# Sheet1.net
KiCad netlist of a schematic drawn in Altium Designer
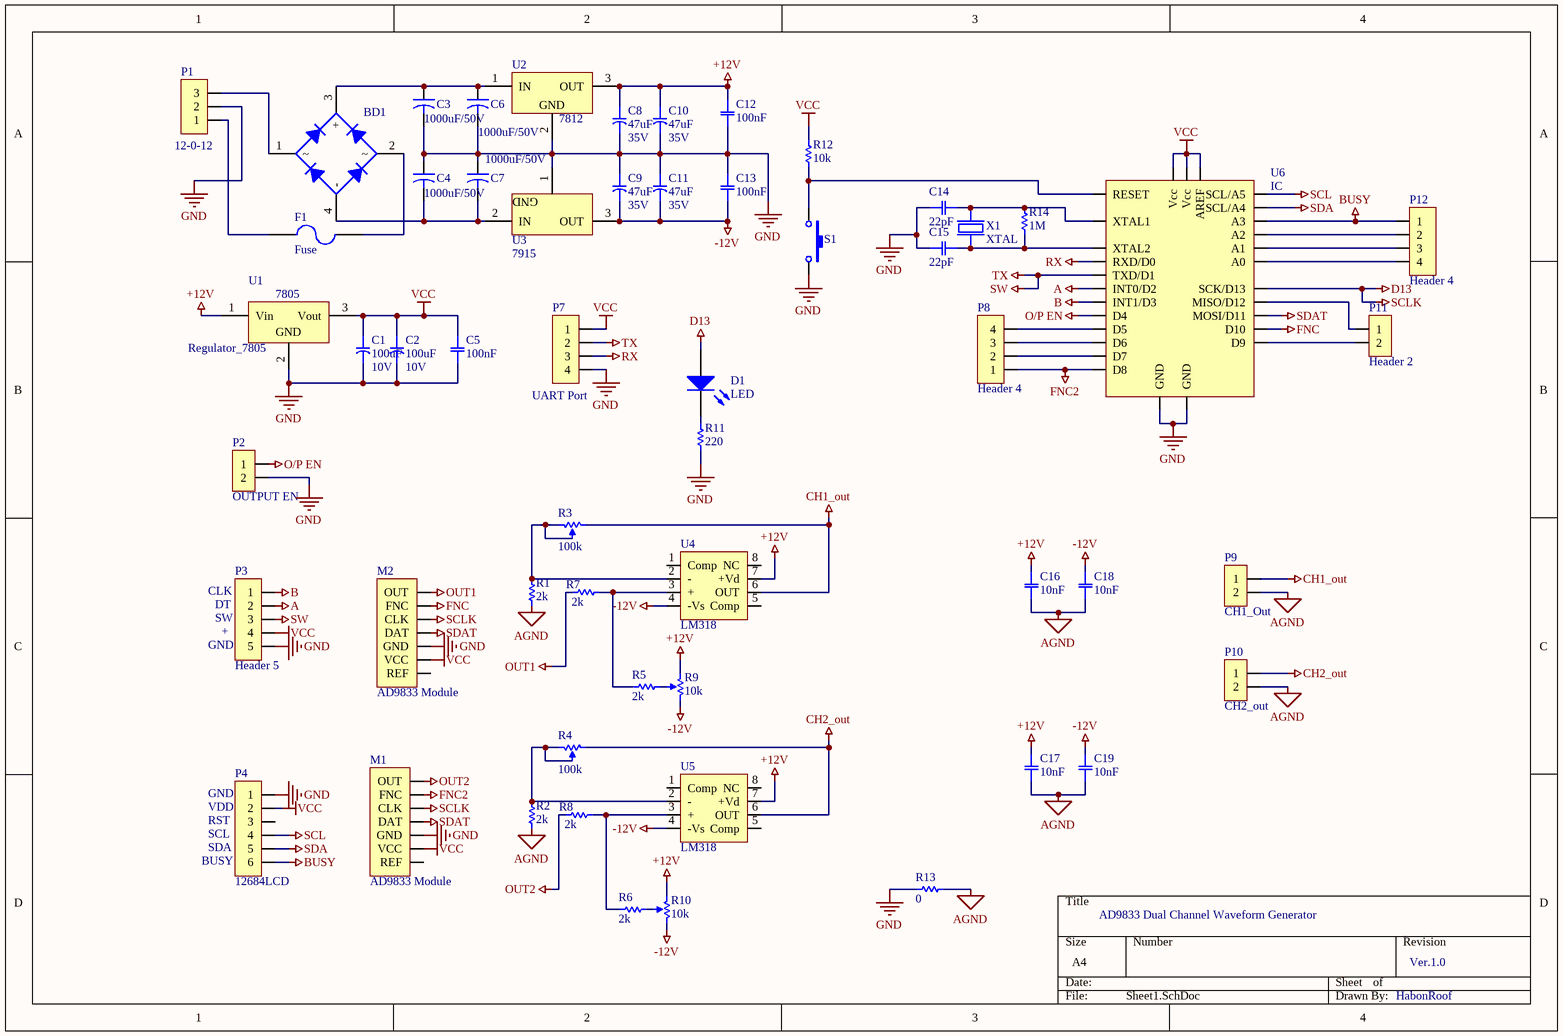
[diagram p0: Sheet1.SchDoc]

(export (version "E")
  (design (tool "Eeschema 10.0.6"))
  (components
    (comp (ref "BD1")
      (value "Bridge")
      (footprint "Bridge_KBL406")
      (description "全波整流器")
      (fields (field (name "PUBLISHER") "Altium Limited"))
      (libsource (lib "Johnson_Lib") (part "Bridge"))
    )
    (comp (ref "C1")
      (value "100uF")
      (footprint "Capacitor_Electrolytic:RAD-100_200")
      (description "JACKON LHK General Purpose")
      (fields
        (field (name "VOLTATGE") "10V")
        (field (name "Comment") "JACKON LHK 100uF/10V")
        (field (name "PUBLISHER") "Altium Limited")
      )
      (libsource (lib "Capacitor_Electrolytic") (part "JACKON LHK 100uF/10V"))
    )
    (comp (ref "C2")
      (value "100uF")
      (footprint "Capacitor_Electrolytic:RAD-100_200")
      (description "JACKON LHK General Purpose")
      (fields
        (field (name "VOLTATGE") "10V")
        (field (name "Comment") "JACKON LHK 100uF/10V")
        (field (name "PUBLISHER") "Altium Limited")
      )
      (libsource (lib "Capacitor_Electrolytic") (part "JACKON LHK 100uF/10V"))
    )
    (comp (ref "C3")
      (value "1000uF/50V")
      (footprint "Cap_M_1000uF/50V")
      (description "有極性電解電容(中)")
      (fields (field (name "PUBLISHER") "Altium Limited"))
      (libsource (lib "Johnson_Lib") (part "Cap_EC_Medium"))
    )
    (comp (ref "C4")
      (value "1000uF/50V")
      (footprint "Cap_M_1000uF/50V")
      (description "有極性電解電容(中)")
      (fields (field (name "PUBLISHER") "Altium Limited"))
      (libsource (lib "Johnson_Lib") (part "Cap_EC_Medium"))
    )
    (comp (ref "C5")
      (value "100nF")
      (footprint "Capacitor_Metallized_Polyester_Film:CAP-200_100*300")
      (description "Metallized Polyester Film Capacitor")
      (fields (field (name "Comment") "100n/100V") (field (name "PUBLISHER") "Altium Limited"))
      (libsource (lib "Capacitor_Metallized_Polyester_Film") (part "100n/100V"))
    )
    (comp (ref "C6")
      (value "1000uF/50V")
      (footprint "Cap_M_1000uF/50V")
      (description "有極性電解電容(中)")
      (fields (field (name "PUBLISHER") "Altium Limited"))
      (libsource (lib "Johnson_Lib") (part "Cap_EC_Medium"))
    )
    (comp (ref "C7")
      (value "1000uF/50V")
      (footprint "Cap_M_1000uF/50V")
      (description "有極性電解電容(中)")
      (fields (field (name "PUBLISHER") "Altium Limited"))
      (libsource (lib "Johnson_Lib") (part "Cap_EC_Medium"))
    )
    (comp (ref "C8")
      (value "47uF")
      (footprint "Capacitor_Electrolytic:RAD-100_200")
      (description "JACKON LHK General Purpose")
      (fields
        (field (name "VOLTATGE") "35V")
        (field (name "Comment") "JACKON LHK 47uF/35V")
        (field (name "PUBLISHER") "Altium Limited")
      )
      (libsource (lib "Capacitor_Electrolytic") (part "JACKON LHK 47uF/35V"))
    )
    (comp (ref "C9")
      (value "47uF")
      (footprint "Capacitor_Electrolytic:RAD-100_200")
      (description "JACKON LHK General Purpose")
      (fields
        (field (name "VOLTATGE") "35V")
        (field (name "Comment") "JACKON LHK 47uF/35V")
        (field (name "PUBLISHER") "Altium Limited")
      )
      (libsource (lib "Capacitor_Electrolytic") (part "JACKON LHK 47uF/35V"))
    )
    (comp (ref "C10")
      (value "47uF")
      (footprint "Capacitor_Electrolytic:RAD-100_200")
      (description "JACKON LHK General Purpose")
      (fields
        (field (name "VOLTATGE") "35V")
        (field (name "Comment") "JACKON LHK 47uF/35V")
        (field (name "PUBLISHER") "Altium Limited")
      )
      (libsource (lib "Capacitor_Electrolytic") (part "JACKON LHK 47uF/35V"))
    )
    (comp (ref "C11")
      (value "47uF")
      (footprint "Capacitor_Electrolytic:RAD-100_200")
      (description "JACKON LHK General Purpose")
      (fields
        (field (name "VOLTATGE") "35V")
        (field (name "Comment") "JACKON LHK 47uF/35V")
        (field (name "PUBLISHER") "Altium Limited")
      )
      (libsource (lib "Capacitor_Electrolytic") (part "JACKON LHK 47uF/35V"))
    )
    (comp (ref "C12")
      (value "100nF")
      (footprint "Capacitor_Metallized_Polyester_Film:CAP-200_100*300")
      (description "Metallized Polyester Film Capacitor")
      (fields (field (name "Comment") "100n/100V") (field (name "PUBLISHER") "Altium Limited"))
      (libsource (lib "Capacitor_Metallized_Polyester_Film") (part "100n/100V"))
    )
    (comp (ref "C13")
      (value "100nF")
      (footprint "Capacitor_Metallized_Polyester_Film:CAP-200_100*300")
      (description "Metallized Polyester Film Capacitor")
      (fields (field (name "Comment") "100n/100V") (field (name "PUBLISHER") "Altium Limited"))
      (libsource (lib "Capacitor_Metallized_Polyester_Film") (part "100n/100V"))
    )
    (comp (ref "C14")
      (value "22pF")
      (footprint "Capacitor_Ceramic:CAP-200_100*300")
      (description "Ceramic Capacitor")
      (fields (field (name "Comment") "22p/1kV") (field (name "PUBLISHER") "Altium Limited"))
      (libsource (lib "Capacitor_Ceramic") (part "22p/1kV"))
    )
    (comp (ref "C15")
      (value "22pF")
      (footprint "Capacitor_Ceramic:CAP-200_100*300")
      (description "Ceramic Capacitor")
      (fields (field (name "Comment") "22p/1kV") (field (name "PUBLISHER") "Altium Limited"))
      (libsource (lib "Capacitor_Ceramic") (part "22p/1kV"))
    )
    (comp (ref "C16")
      (value "10nF")
      (footprint "Capacitor_Metallized_Polyester_Film:CAP-200_100*300")
      (description "Metallized Polyester Film Capacitor")
      (fields (field (name "Comment") "100n/100V") (field (name "PUBLISHER") "Altium Limited"))
      (libsource (lib "Capacitor_Metallized_Polyester_Film") (part "100n/100V"))
    )
    (comp (ref "C17")
      (value "10nF")
      (footprint "Capacitor_Metallized_Polyester_Film:CAP-200_100*300")
      (description "Metallized Polyester Film Capacitor")
      (fields (field (name "Comment") "100n/100V") (field (name "PUBLISHER") "Altium Limited"))
      (libsource (lib "Capacitor_Metallized_Polyester_Film") (part "100n/100V"))
    )
    (comp (ref "C18")
      (value "10nF")
      (footprint "Capacitor_Metallized_Polyester_Film:CAP-200_100*300")
      (description "Metallized Polyester Film Capacitor")
      (fields (field (name "Comment") "100n/100V") (field (name "PUBLISHER") "Altium Limited"))
      (libsource (lib "Capacitor_Metallized_Polyester_Film") (part "100n/100V"))
    )
    (comp (ref "C19")
      (value "10nF")
      (footprint "Capacitor_Metallized_Polyester_Film:CAP-200_100*300")
      (description "Metallized Polyester Film Capacitor")
      (fields (field (name "Comment") "100n/100V") (field (name "PUBLISHER") "Altium Limited"))
      (libsource (lib "Capacitor_Metallized_Polyester_Film") (part "100n/100V"))
    )
    (comp (ref "D1")
      (value "LED")
      (footprint "LED_SMALL")
      (fields (field (name "PUBLISHER") "Altium Limited"))
      (libsource (lib "Johnson_Lib") (part "LED"))
    )
    (comp (ref "F1")
      (value "Fuse")
      (footprint "FUSE")
      (fields (field (name "PUBLISHER") "Altium Limited"))
      (libsource (lib "Johnson_Lib") (part "Fuse"))
    )
    (comp (ref "M1")
      (value "AD9833 Module")
      (footprint "AD9833")
      (libsource (lib "Johnson_Lib") (part "AD9833 Module"))
    )
    (comp (ref "M2")
      (value "AD9833 Module")
      (footprint "AD9833")
      (libsource (lib "Johnson_Lib") (part "AD9833 Module"))
    )
    (comp (ref "P1")
      (value "12-0-12")
      (footprint "HDR1X3")
      (description "Header, 3-Pin")
      (fields (field (name "PUBLISHER") "Altium Limited"))
      (libsource (lib "Johnson_Lib") (part "Header 3"))
    )
    (comp (ref "P2")
      (value "OUTPUT EN")
      (footprint "HDR1X2")
      (description "Header, 2-Pin")
      (fields (field (name "PUBLISHER") "Altium Limited"))
      (libsource (lib "Johnson_Lib") (part "Header 2"))
    )
    (comp (ref "P3")
      (value "Header 5")
      (footprint "HDR1X5")
      (description "Header, 5-Pin")
      (fields (field (name "PUBLISHER") "Altium Limited"))
      (libsource (lib "Johnson_Lib") (part "Header 5"))
    )
    (comp (ref "P4")
      (value "12684LCD")
      (footprint "HDR1X6")
      (description "Header, 6-Pin")
      (fields (field (name "PUBLISHER") "Altium Limited"))
      (libsource (lib "Johnson_Lib") (part "Header 6"))
    )
    (comp (ref "P7")
      (value "UART Port")
      (footprint "HDR1X4H")
      (description "Header, 4-Pin")
      (fields (field (name "PUBLISHER") "Altium Limited"))
      (libsource (lib "") (part "Header 4_1"))
    )
    (comp (ref "P8")
      (value "Header 4")
      (footprint "HDR1X4")
      (description "Header, 4-Pin")
      (fields (field (name "PUBLISHER") "Altium Limited"))
      (libsource (lib "") (part "Header 4_2"))
    )
    (comp (ref "P9")
      (value "CH1_Out")
      (footprint "HDR1X2")
      (description "Header, 2-Pin")
      (fields (field (name "PUBLISHER") "Altium Limited"))
      (libsource (lib "Johnson_Lib") (part "Header 2"))
    )
    (comp (ref "P10")
      (value "CH2_out")
      (footprint "HDR1X2")
      (description "Header, 2-Pin")
      (fields (field (name "PUBLISHER") "Altium Limited"))
      (libsource (lib "Johnson_Lib") (part "Header 2"))
    )
    (comp (ref "P11")
      (value "Header 2")
      (footprint "HDR1X2")
      (description "Header, 2-Pin")
      (fields (field (name "PUBLISHER") "Altium Limited"))
      (libsource (lib "") (part "Header 2_1"))
    )
    (comp (ref "P12")
      (value "Header 4")
      (footprint "HDR1X4")
      (description "Header, 4-Pin")
      (fields (field (name "PUBLISHER") "Altium Limited"))
      (libsource (lib "Johnson_Lib") (part "Header 4"))
    )
    (comp (ref "R1")
      (value "2k")
      (footprint "R-0.25W")
      (description "固定電阻")
      (fields (field (name "PUBLISHER") "Altium Limited"))
      (libsource (lib "Johnson_Lib") (part "Resistor"))
    )
    (comp (ref "R2")
      (value "2k")
      (footprint "R-0.25W")
      (description "固定電阻")
      (fields (field (name "PUBLISHER") "Altium Limited"))
      (libsource (lib "Johnson_Lib") (part "Resistor"))
    )
    (comp (ref "R3")
      (value "100k")
      (footprint "VR-Medium")
      (description "可變電阻")
      (fields (field (name "PUBLISHER") "Altium Limited"))
      (libsource (lib "Johnson_Lib") (part "Resistor_Potentiometer"))
    )
    (comp (ref "R4")
      (value "100k")
      (footprint "VR-Medium")
      (description "可變電阻")
      (fields (field (name "PUBLISHER") "Altium Limited"))
      (libsource (lib "Johnson_Lib") (part "Resistor_Potentiometer"))
    )
    (comp (ref "R5")
      (value "2k")
      (footprint "R-0.25W")
      (description "固定電阻")
      (fields (field (name "PUBLISHER") "Altium Limited"))
      (libsource (lib "Johnson_Lib") (part "Resistor"))
    )
    (comp (ref "R6")
      (value "2k")
      (footprint "R-0.25W")
      (description "固定電阻")
      (fields (field (name "PUBLISHER") "Altium Limited"))
      (libsource (lib "Johnson_Lib") (part "Resistor"))
    )
    (comp (ref "R7")
      (value "2k")
      (footprint "R-0.25W")
      (description "固定電阻")
      (fields (field (name "PUBLISHER") "Altium Limited"))
      (libsource (lib "Johnson_Lib") (part "Resistor"))
    )
    (comp (ref "R8")
      (value "2k")
      (footprint "R-0.25W")
      (description "固定電阻")
      (fields (field (name "PUBLISHER") "Altium Limited"))
      (libsource (lib "Johnson_Lib") (part "Resistor"))
    )
    (comp (ref "R9")
      (value "10k")
      (footprint "VR-Medium")
      (description "可變電阻")
      (fields (field (name "PUBLISHER") "Altium Limited"))
      (libsource (lib "Johnson_Lib") (part "Resistor_Potentiometer"))
    )
    (comp (ref "R10")
      (value "10k")
      (footprint "VR-Medium")
      (description "可變電阻")
      (fields (field (name "PUBLISHER") "Altium Limited"))
      (libsource (lib "Johnson_Lib") (part "Resistor_Potentiometer"))
    )
    (comp (ref "R11")
      (value "220")
      (footprint "RS0805")
      (description "固定電阻")
      (fields (field (name "PUBLISHER") "Altium Limited"))
      (libsource (lib "Johnson_Lib") (part "Resistor"))
    )
    (comp (ref "R12")
      (value "10k")
      (footprint "R-0.25W")
      (description "固定電阻")
      (fields (field (name "PUBLISHER") "Altium Limited"))
      (libsource (lib "Johnson_Lib") (part "Resistor"))
    )
    (comp (ref "R13")
      (value "0")
      (footprint "RS0805")
      (description "固定電阻")
      (fields (field (name "PUBLISHER") "Altium Limited"))
      (libsource (lib "Johnson_Lib") (part "Resistor"))
    )
    (comp (ref "R14")
      (value "1M")
      (footprint "R-0.25W")
      (description "固定電阻")
      (fields (field (name "PUBLISHER") "Altium Limited"))
      (libsource (lib "Johnson_Lib") (part "Resistor"))
    )
    (comp (ref "S1")
      (value "SW PB")
      (footprint "Button")
      (description "Button Switch")
      (libsource (lib "Johnson_Lib") (part "SW PB"))
    )
    (comp (ref "U1")
      (value "Regulator_7805")
      (footprint "TO-220")
      (description "Voltage Regulator")
      (fields (field (name "PUBLISHER") "Altium Limited"))
      (libsource (lib "Johnson_Lib") (part "Regulator-7805"))
    )
    (comp (ref "U2")
      (value "7812")
      (footprint "IC:TO-220")
      (description "THREE TERMINAL POSITIVE VOLTAGE REGULATORS")
      (libsource (lib "IC") (part "7805"))
    )
    (comp (ref "U3")
      (value "7915")
      (footprint "IC:TO-220")
      (description "THREE TERMINAL NEGATIVE VOLTAGE REGULATORS")
      (libsource (lib "IC") (part "7915"))
    )
    (comp (ref "U4")
      (value "LM318")
      (footprint "DIP-8")
      (description "Single OPA SR:50v/uS")
      (libsource (lib "Johnson_Lib") (part "LM318"))
    )
    (comp (ref "U5")
      (value "LM318")
      (footprint "DIP-8")
      (description "Single OPA SR:50v/uS")
      (libsource (lib "Johnson_Lib") (part "LM318"))
    )
    (comp (ref "U6")
      (value "IC")
      (footprint "DIP-28")
      (description "Arduino controller")
      (libsource (lib "Johnson_Lib") (part "Atmega328P"))
    )
    (comp (ref "X1")
      (value "XTAL")
      (footprint "HC49-4H")
      (description "Crystal Oscillator")
      (libsource (lib "Johnson_Lib") (part "XTAL"))
    )
  )
  (nets
    (net (code "1") (name "+12V") (class "Default")
      (node (ref "C10") (pin "1") (pinfunction "1_1") (pintype "passive"))
      (node (ref "C12") (pin "2") (pinfunction "2_2") (pintype "passive"))
      (node (ref "C16") (pin "1") (pinfunction "1_1") (pintype "passive"))
      (node (ref "C17") (pin "1") (pinfunction "1_1") (pintype "passive"))
      (node (ref "C8") (pin "1") (pinfunction "1_1") (pintype "passive"))
      (node (ref "R10") (pin "3") (pinfunction "3_3") (pintype "passive"))
      (node (ref "R9") (pin "3") (pinfunction "3_3") (pintype "passive"))
      (node (ref "U1") (pin "1") (pinfunction "Vin_1") (pintype "passive"))
      (node (ref "U2") (pin "3") (pinfunction "OUT_3") (pintype "passive"))
      (node (ref "U4") (pin "7") (pinfunction "+Vd_7") (pintype "passive"))
      (node (ref "U5") (pin "7") (pinfunction "+Vd_7") (pintype "passive"))
    )
    (net (code "2") (name "-12V") (class "Default")
      (node (ref "C11") (pin "2") (pinfunction "2_2") (pintype "passive"))
      (node (ref "C13") (pin "1") (pinfunction "1_1") (pintype "passive"))
      (node (ref "C18") (pin "2") (pinfunction "2_2") (pintype "passive"))
      (node (ref "C19") (pin "2") (pinfunction "2_2") (pintype "passive"))
      (node (ref "C9") (pin "2") (pinfunction "2_2") (pintype "passive"))
      (node (ref "R10") (pin "1") (pinfunction "1_1") (pintype "passive"))
      (node (ref "R9") (pin "1") (pinfunction "1_1") (pintype "passive"))
      (node (ref "U3") (pin "3") (pinfunction "OUT_3") (pintype "passive"))
      (node (ref "U4") (pin "4") (pinfunction "-Vs_4") (pintype "passive"))
      (node (ref "U5") (pin "4") (pinfunction "-Vs_4") (pintype "passive"))
    )
    (net (code "3") (name "A") (class "Default")
      (node (ref "P3") (pin "2") (pinfunction "2_2") (pintype "passive"))
      (node (ref "U6") (pin "4") (pinfunction "INT0/D2_4") (pintype "passive"))
    )
    (net (code "4") (name "AGND") (class "Default")
      (node (ref "C16") (pin "2") (pinfunction "2_2") (pintype "passive"))
      (node (ref "C17") (pin "2") (pinfunction "2_2") (pintype "passive"))
      (node (ref "C18") (pin "1") (pinfunction "1_1") (pintype "passive"))
      (node (ref "C19") (pin "1") (pinfunction "1_1") (pintype "passive"))
      (node (ref "P10") (pin "2") (pinfunction "2_2") (pintype "passive"))
      (node (ref "P9") (pin "2") (pinfunction "2_2") (pintype "passive"))
      (node (ref "R1") (pin "2") (pinfunction "2_2") (pintype "passive"))
      (node (ref "R13") (pin "1") (pinfunction "1_1") (pintype "passive"))
      (node (ref "R2") (pin "2") (pinfunction "2_2") (pintype "passive"))
    )
    (net (code "5") (name "B") (class "Default")
      (node (ref "P3") (pin "1") (pinfunction "1_1") (pintype "passive"))
      (node (ref "U6") (pin "5") (pinfunction "INT1/D3_5") (pintype "passive"))
    )
    (net (code "6") (name "BUSY") (class "Default")
      (node (ref "P12") (pin "1") (pinfunction "1_1") (pintype "passive"))
      (node (ref "P4") (pin "6") (pinfunction "6_6") (pintype "passive"))
      (node (ref "U6") (pin "26") (pinfunction "A3_26") (pintype "passive"))
    )
    (net (code "7") (name "CH1_out") (class "Default")
      (node (ref "P9") (pin "1") (pinfunction "1_1") (pintype "passive"))
      (node (ref "R3") (pin "1") (pinfunction "1_1") (pintype "passive"))
      (node (ref "U4") (pin "6") (pinfunction "OUT_6") (pintype "passive"))
    )
    (net (code "8") (name "CH2_out") (class "Default")
      (node (ref "P10") (pin "1") (pinfunction "1_1") (pintype "passive"))
      (node (ref "R4") (pin "1") (pinfunction "1_1") (pintype "passive"))
      (node (ref "U5") (pin "6") (pinfunction "OUT_6") (pintype "passive"))
    )
    (net (code "9") (name "D13") (class "Default")
      (node (ref "D1") (pin "1") (pinfunction "A_1") (pintype "passive"))
      (node (ref "M1") (pin "5") (pinfunction "CLK_5") (pintype "passive"))
      (node (ref "M2") (pin "5") (pinfunction "CLK_5") (pintype "passive"))
      (node (ref "U6") (pin "19") (pinfunction "SCK/D13_19") (pintype "passive"))
    )
    (net (code "10") (name "FNC") (class "Default")
      (node (ref "M2") (pin "6") (pinfunction "FNC_6") (pintype "passive"))
      (node (ref "U6") (pin "16") (pinfunction "D10_16") (pintype "passive"))
    )
    (net (code "11") (name "FNC2") (class "Default")
      (node (ref "M1") (pin "6") (pinfunction "FNC_6") (pintype "passive"))
      (node (ref "P8") (pin "1") (pinfunction "1_1") (pintype "passive"))
      (node (ref "U6") (pin "14") (pinfunction "D8_14") (pintype "passive"))
    )
    (net (code "12") (name "GND") (class "Default")
      (node (ref "C1") (pin "2") (pinfunction "2_2") (pintype "passive"))
      (node (ref "C10") (pin "2") (pinfunction "2_2") (pintype "passive"))
      (node (ref "C11") (pin "1") (pinfunction "1_1") (pintype "passive"))
      (node (ref "C12") (pin "1") (pinfunction "1_1") (pintype "passive"))
      (node (ref "C13") (pin "2") (pinfunction "2_2") (pintype "passive"))
      (node (ref "C14") (pin "1") (pinfunction "1_1") (pintype "passive"))
      (node (ref "C15") (pin "1") (pinfunction "1_1") (pintype "passive"))
      (node (ref "C2") (pin "2") (pinfunction "2_2") (pintype "passive"))
      (node (ref "C3") (pin "2") (pinfunction "2_2") (pintype "passive"))
      (node (ref "C4") (pin "1") (pinfunction "1_1") (pintype "passive"))
      (node (ref "C5") (pin "1") (pinfunction "1_1") (pintype "passive"))
      (node (ref "C6") (pin "2") (pinfunction "2_2") (pintype "passive"))
      (node (ref "C7") (pin "1") (pinfunction "1_1") (pintype "passive"))
      (node (ref "C8") (pin "2") (pinfunction "2_2") (pintype "passive"))
      (node (ref "C9") (pin "1") (pinfunction "1_1") (pintype "passive"))
      (node (ref "M1") (pin "3") (pinfunction "GND_3") (pintype "passive"))
      (node (ref "M2") (pin "3") (pinfunction "GND_3") (pintype "passive"))
      (node (ref "P1") (pin "2") (pinfunction "2_2") (pintype "passive"))
      (node (ref "P2") (pin "2") (pinfunction "2_2") (pintype "passive"))
      (node (ref "P3") (pin "5") (pinfunction "5_5") (pintype "passive"))
      (node (ref "P4") (pin "1") (pinfunction "1_1") (pintype "passive"))
      (node (ref "P7") (pin "4") (pinfunction "4_4") (pintype "passive"))
      (node (ref "R11") (pin "2") (pinfunction "2_2") (pintype "passive"))
      (node (ref "R13") (pin "2") (pinfunction "2_2") (pintype "passive"))
      (node (ref "S1") (pin "2") (pinfunction "2_2") (pintype "passive"))
      (node (ref "U1") (pin "2") (pinfunction "GND_2") (pintype "passive"))
      (node (ref "U2") (pin "2") (pinfunction "GND_2") (pintype "passive"))
      (node (ref "U3") (pin "1") (pinfunction "GND_1") (pintype "passive"))
      (node (ref "U6") (pin "22") (pinfunction "GND_22") (pintype "passive"))
      (node (ref "U6") (pin "8") (pinfunction "GND_8") (pintype "passive"))
    )
    (net (code "13") (name "Net-(BD1-+)") (class "Default")
      (node (ref "BD1") (pin "3") (pinfunction "+_3") (pintype "passive"))
      (node (ref "C3") (pin "1") (pinfunction "1_1") (pintype "passive"))
      (node (ref "C6") (pin "1") (pinfunction "1_1") (pintype "passive"))
      (node (ref "U2") (pin "1") (pinfunction "IN_1") (pintype "passive"))
    )
    (net (code "14") (name "Net-(BD1--)") (class "Default")
      (node (ref "BD1") (pin "4") (pinfunction "-_4") (pintype "passive"))
      (node (ref "C4") (pin "2") (pinfunction "2_2") (pintype "passive"))
      (node (ref "C7") (pin "2") (pinfunction "2_2") (pintype "passive"))
      (node (ref "U3") (pin "2") (pinfunction "IN_2") (pintype "passive"))
    )
    (net (code "15") (name "Net-(BD1-~-Pad1)") (class "Default")
      (node (ref "BD1") (pin "1") (pinfunction "~_1") (pintype "passive"))
      (node (ref "P1") (pin "3") (pinfunction "3_3") (pintype "passive"))
    )
    (net (code "16") (name "Net-(BD1-~-Pad2)") (class "Default")
      (node (ref "BD1") (pin "2") (pinfunction "~_2") (pintype "passive"))
      (node (ref "F1") (pin "2") (pinfunction "2_2") (pintype "passive"))
    )
    (net (code "17") (name "Net-(D1-K)") (class "Default")
      (node (ref "D1") (pin "2") (pinfunction "K_2") (pintype "passive"))
      (node (ref "R11") (pin "1") (pinfunction "1_1") (pintype "passive"))
    )
    (net (code "18") (name "Net-(F1-Pad1)") (class "Default")
      (node (ref "F1") (pin "1") (pinfunction "1_1") (pintype "passive"))
      (node (ref "P1") (pin "1") (pinfunction "1_1") (pintype "passive"))
    )
    (net (code "19") (name "Net-(R5-Pad2)") (class "Default")
      (node (ref "R5") (pin "2") (pinfunction "2_2") (pintype "passive"))
      (node (ref "R9") (pin "2") (pinfunction "2_2") (pintype "passive"))
    )
    (net (code "20") (name "Net-(R10-Pad2)") (class "Default")
      (node (ref "R10") (pin "2") (pinfunction "2_2") (pintype "passive"))
      (node (ref "R6") (pin "2") (pinfunction "2_2") (pintype "passive"))
    )
    (net (code "21") (name "Net-(U4-+)") (class "Default")
      (node (ref "R5") (pin "1") (pinfunction "1_1") (pintype "passive"))
      (node (ref "R7") (pin "1") (pinfunction "1_1") (pintype "passive"))
      (node (ref "U4") (pin "3") (pinfunction "+_3") (pintype "passive"))
    )
    (net (code "22") (name "Net-(U4--)") (class "Default")
      (node (ref "R1") (pin "1") (pinfunction "1_1") (pintype "passive"))
      (node (ref "R3") (pin "2") (pinfunction "2_2") (pintype "passive"))
      (node (ref "R3") (pin "3") (pinfunction "3_3") (pintype "passive"))
      (node (ref "U4") (pin "2") (pinfunction "-_2") (pintype "passive"))
    )
    (net (code "23") (name "Net-(U5-+)") (class "Default")
      (node (ref "R6") (pin "1") (pinfunction "1_1") (pintype "passive"))
      (node (ref "R8") (pin "1") (pinfunction "1_1") (pintype "passive"))
      (node (ref "U5") (pin "3") (pinfunction "+_3") (pintype "passive"))
    )
    (net (code "24") (name "Net-(U5--)") (class "Default")
      (node (ref "R2") (pin "1") (pinfunction "1_1") (pintype "passive"))
      (node (ref "R4") (pin "2") (pinfunction "2_2") (pintype "passive"))
      (node (ref "R4") (pin "3") (pinfunction "3_3") (pintype "passive"))
      (node (ref "U5") (pin "2") (pinfunction "-_2") (pintype "passive"))
    )
    (net (code "25") (name "Net-(U6-A0)") (class "Default")
      (node (ref "P12") (pin "4") (pinfunction "4_4") (pintype "passive"))
      (node (ref "U6") (pin "23") (pinfunction "A0_23") (pintype "passive"))
    )
    (net (code "26") (name "Net-(U6-A1)") (class "Default")
      (node (ref "P12") (pin "3") (pinfunction "3_3") (pintype "passive"))
      (node (ref "U6") (pin "24") (pinfunction "A1_24") (pintype "passive"))
    )
    (net (code "27") (name "Net-(U6-A2)") (class "Default")
      (node (ref "P12") (pin "2") (pinfunction "2_2") (pintype "passive"))
      (node (ref "U6") (pin "25") (pinfunction "A2_25") (pintype "passive"))
    )
    (net (code "28") (name "Net-(U6-D5)") (class "Default")
      (node (ref "P8") (pin "4") (pinfunction "4_4") (pintype "passive"))
      (node (ref "U6") (pin "11") (pinfunction "D5_11") (pintype "passive"))
    )
    (net (code "29") (name "Net-(U6-D6)") (class "Default")
      (node (ref "P8") (pin "3") (pinfunction "3_3") (pintype "passive"))
      (node (ref "U6") (pin "12") (pinfunction "D6_12") (pintype "passive"))
    )
    (net (code "30") (name "Net-(U6-D7)") (class "Default")
      (node (ref "P8") (pin "2") (pinfunction "2_2") (pintype "passive"))
      (node (ref "U6") (pin "13") (pinfunction "D7_13") (pintype "passive"))
    )
    (net (code "31") (name "Net-(U6-D9)") (class "Default")
      (node (ref "P11") (pin "2") (pinfunction "2_2") (pintype "passive"))
      (node (ref "U6") (pin "15") (pinfunction "D9_15") (pintype "passive"))
    )
    (net (code "32") (name "Net-(U6-MISO{slash}D12)") (class "Default")
      (node (ref "P11") (pin "1") (pinfunction "1_1") (pintype "passive"))
      (node (ref "U6") (pin "18") (pinfunction "MISO/D12_18") (pintype "passive"))
    )
    (net (code "33") (name "Net-(U6-RESET)") (class "Default")
      (node (ref "R12") (pin "1") (pinfunction "1_1") (pintype "passive"))
      (node (ref "S1") (pin "1") (pinfunction "1_1") (pintype "passive"))
      (node (ref "U6") (pin "1") (pinfunction "RESET_1") (pintype "passive"))
    )
    (net (code "34") (name "Net-(U6-XTAL1)") (class "Default")
      (node (ref "C14") (pin "2") (pinfunction "2_2") (pintype "passive"))
      (node (ref "R14") (pin "1") (pinfunction "1_1") (pintype "passive"))
      (node (ref "U6") (pin "9") (pinfunction "XTAL1_9") (pintype "passive"))
      (node (ref "X1") (pin "1") (pinfunction "1_1") (pintype "passive"))
    )
    (net (code "35") (name "Net-(U6-XTAL2)") (class "Default")
      (node (ref "C15") (pin "2") (pinfunction "2_2") (pintype "passive"))
      (node (ref "R14") (pin "2") (pinfunction "2_2") (pintype "passive"))
      (node (ref "U6") (pin "10") (pinfunction "XTAL2_10") (pintype "passive"))
      (node (ref "X1") (pin "2") (pinfunction "2_2") (pintype "passive"))
    )
    (net (code "36") (name "OUT1") (class "Default")
      (node (ref "M2") (pin "7") (pinfunction "OUT_7") (pintype "passive"))
      (node (ref "R7") (pin "2") (pinfunction "2_2") (pintype "passive"))
    )
    (net (code "37") (name "OUT2") (class "Default")
      (node (ref "M1") (pin "7") (pinfunction "OUT_7") (pintype "passive"))
      (node (ref "R8") (pin "2") (pinfunction "2_2") (pintype "passive"))
    )
    (net (code "38") (name "O{slash}P EN") (class "Default")
      (node (ref "P2") (pin "1") (pinfunction "1_1") (pintype "passive"))
      (node (ref "U6") (pin "6") (pinfunction "D4_6") (pintype "passive"))
    )
    (net (code "39") (name "RX") (class "Default")
      (node (ref "P7") (pin "3") (pinfunction "3_3") (pintype "passive"))
      (node (ref "U6") (pin "2") (pinfunction "RXD/D0_2") (pintype "passive"))
    )
    (net (code "40") (name "SCL") (class "Default")
      (node (ref "P4") (pin "4") (pinfunction "4_4") (pintype "passive"))
      (node (ref "U6") (pin "28") (pinfunction "SCL/A5_28") (pintype "passive"))
    )
    (net (code "41") (name "SDA") (class "Default")
      (node (ref "P4") (pin "5") (pinfunction "5_5") (pintype "passive"))
      (node (ref "U6") (pin "27") (pinfunction "SCL/A4_27") (pintype "passive"))
    )
    (net (code "42") (name "SDAT") (class "Default")
      (node (ref "M1") (pin "4") (pinfunction "DAT_4") (pintype "passive"))
      (node (ref "M2") (pin "4") (pinfunction "DAT_4") (pintype "passive"))
      (node (ref "U6") (pin "17") (pinfunction "MOSI/D11_17") (pintype "passive"))
    )
    (net (code "43") (name "SW") (class "Default")
      (node (ref "P3") (pin "3") (pinfunction "3_3") (pintype "passive"))
      (node (ref "P7") (pin "2") (pinfunction "2_2") (pintype "passive"))
      (node (ref "U6") (pin "3") (pinfunction "TXD/D1_3") (pintype "passive"))
    )
    (net (code "44") (name "VCC") (class "Default")
      (node (ref "C1") (pin "1") (pinfunction "1_1") (pintype "passive"))
      (node (ref "C2") (pin "1") (pinfunction "1_1") (pintype "passive"))
      (node (ref "C5") (pin "2") (pinfunction "2_2") (pintype "passive"))
      (node (ref "M1") (pin "2") (pinfunction "VCC_2") (pintype "passive"))
      (node (ref "M2") (pin "2") (pinfunction "VCC_2") (pintype "passive"))
      (node (ref "P3") (pin "4") (pinfunction "4_4") (pintype "passive"))
      (node (ref "P4") (pin "2") (pinfunction "2_2") (pintype "passive"))
      (node (ref "P7") (pin "1") (pinfunction "1_1") (pintype "passive"))
      (node (ref "R12") (pin "2") (pinfunction "2_2") (pintype "passive"))
      (node (ref "U1") (pin "3") (pinfunction "Vout_3") (pintype "passive"))
      (node (ref "U6") (pin "20") (pinfunction "Vcc_20") (pintype "passive"))
      (node (ref "U6") (pin "21") (pinfunction "AREF_21") (pintype "passive"))
      (node (ref "U6") (pin "7") (pinfunction "Vcc_7") (pintype "passive"))
    )
    (net (code "45") (name "unconnected-(M1-REF-Pad1)") (class "Default")
      (node (ref "M1") (pin "1") (pinfunction "REF_1") (pintype "passive"))
    )
    (net (code "46") (name "unconnected-(M2-REF-Pad1)") (class "Default")
      (node (ref "M2") (pin "1") (pinfunction "REF_1") (pintype "passive"))
    )
    (net (code "47") (name "unconnected-(P4-Pad3)") (class "Default")
      (node (ref "P4") (pin "3") (pinfunction "3_3") (pintype "passive"))
    )
    (net (code "48") (name "unconnected-(U4-Comp-Pad1)") (class "Default")
      (node (ref "U4") (pin "1") (pinfunction "Comp_1") (pintype "passive"))
    )
    (net (code "49") (name "unconnected-(U4-Comp-Pad5)") (class "Default")
      (node (ref "U4") (pin "5") (pinfunction "Comp_5") (pintype "passive"))
    )
    (net (code "50") (name "unconnected-(U4-NC-Pad8)") (class "Default")
      (node (ref "U4") (pin "8") (pinfunction "NC_8") (pintype "passive"))
    )
    (net (code "51") (name "unconnected-(U5-Comp-Pad1)") (class "Default")
      (node (ref "U5") (pin "1") (pinfunction "Comp_1") (pintype "passive"))
    )
    (net (code "52") (name "unconnected-(U5-Comp-Pad5)") (class "Default")
      (node (ref "U5") (pin "5") (pinfunction "Comp_5") (pintype "passive"))
    )
    (net (code "53") (name "unconnected-(U5-NC-Pad8)") (class "Default")
      (node (ref "U5") (pin "8") (pinfunction "NC_8") (pintype "passive"))
    )
  )
)
